# mavroOBD-Power.net
KiCad netlist of a schematic drawn in EAGLE
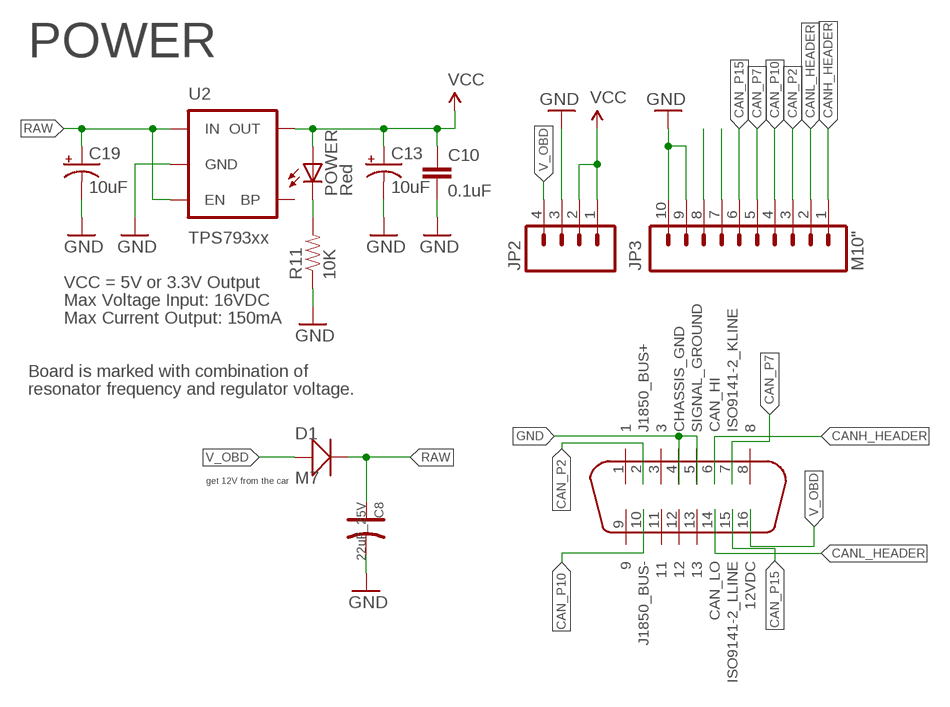
[diagram p0: schematic, sheet 1]

(export (version "E")
  (design (tool "Eeschema 10.0.6"))
  (components
    (comp (ref "C8")
      (value "22uF_25V")
      (footprint "eagle-import:ELECTRO-SMD-B-4.8MM")
      (libsource (lib "eagle-import") (part "CAP-ELECTRO-B"))
    )
    (comp (ref "C10")
      (value "0.1uF")
      (footprint "eagle-import:0603-CAP")
      (libsource (lib "eagle-import") (part "CAP0603-CAP"))
    )
    (comp (ref "C13")
      (value "10uF")
      (footprint "eagle-import:EIA3216")
      (libsource (lib "eagle-import") (part "CAP_POL1206"))
    )
    (comp (ref "C19")
      (value "10uF")
      (footprint "eagle-import:EIA3216")
      (libsource (lib "eagle-import") (part "CAP_POL1206"))
    )
    (comp (ref "D1")
      (value "M7")
      (footprint "eagle-import:D2010")
      (libsource (lib "eagle-import") (part "D-SMA"))
    )
    (comp (ref "JP2")
      (value "M04PTH")
      (footprint "eagle-import:1X04")
      (libsource (lib "eagle-import") (part "M04PTH"))
    )
    (comp (ref "JP3")
      (value "M10\"")
      (footprint "eagle-import:1X10")
      (libsource (lib "eagle-import") (part "M10{dblquote}"))
    )
    (comp (ref "POWER")
      (value "Red")
      (footprint "eagle-import:0603-LED-ALT1")
      (libsource (lib "eagle-import") (part "LED"))
    )
    (comp (ref "R11")
      (value "10K")
      (footprint "eagle-import:0603-RES")
      (libsource (lib "eagle-import") (part "RESISTOR0603-RES"))
    )
    (comp (ref "U$1")
      (value "ODBII-CON")
      (footprint "eagle-import:OBDII-CON")
      (libsource (lib "eagle-import") (part "ODBII-CON"))
    )
    (comp (ref "U2")
      (value "TPS793xx")
      (footprint "eagle-import:SOT23-5")
      (libsource (lib "eagle-import") (part "V_REG_LDOSMD"))
    )
  )
  (nets
    (net (code "1") (name "CANH_HEADER") (class "Default")
      (node (ref "JP3") (pin "1") (pinfunction "1_1") (pintype "passive"))
      (node (ref "U$1") (pin "6") (pinfunction "CAN_HI_6") (pintype "bidirectional"))
    )
    (net (code "2") (name "CANL_HEADER") (class "Default")
      (node (ref "JP3") (pin "2") (pinfunction "2_2") (pintype "passive"))
      (node (ref "U$1") (pin "14") (pinfunction "CAN_LO_14") (pintype "bidirectional"))
    )
    (net (code "3") (name "CAN_P2") (class "Default")
      (node (ref "JP3") (pin "3") (pinfunction "3_3") (pintype "passive"))
      (node (ref "U$1") (pin "2") (pinfunction "J1850_BUS+_2") (pintype "bidirectional"))
    )
    (net (code "4") (name "CAN_P7") (class "Default")
      (node (ref "JP3") (pin "5") (pinfunction "5_5") (pintype "passive"))
      (node (ref "U$1") (pin "7") (pinfunction "ISO9141-2_KLINE_7") (pintype "bidirectional"))
    )
    (net (code "5") (name "CAN_P10") (class "Default")
      (node (ref "JP3") (pin "4") (pinfunction "4_4") (pintype "passive"))
      (node (ref "U$1") (pin "10") (pinfunction "J1850_BUS-_10") (pintype "bidirectional"))
    )
    (net (code "6") (name "CAN_P15") (class "Default")
      (node (ref "JP3") (pin "6") (pinfunction "6_6") (pintype "passive"))
      (node (ref "U$1") (pin "15") (pinfunction "ISO9141-2_LLINE_15") (pintype "bidirectional"))
    )
    (net (code "7") (name "GND") (class "Default")
      (node (ref "C10") (pin "2") (pinfunction "2_2") (pintype "passive"))
      (node (ref "C13") (pin "C") (pinfunction "-_C") (pintype "passive"))
      (node (ref "C19") (pin "C") (pinfunction "-_C") (pintype "passive"))
      (node (ref "C8") (pin "-") (pinfunction "-_-") (pintype "passive"))
      (node (ref "JP2") (pin "3") (pinfunction "3_3") (pintype "passive"))
      (node (ref "JP3") (pin "10") (pinfunction "10_10") (pintype "passive"))
      (node (ref "JP3") (pin "9") (pinfunction "9_9") (pintype "passive"))
      (node (ref "R11") (pin "1") (pinfunction "1_1") (pintype "passive"))
      (node (ref "U$1") (pin "4") (pinfunction "CHASSIS_GND_4") (pintype "bidirectional"))
      (node (ref "U$1") (pin "5") (pinfunction "SIGNAL_GROUND_5") (pintype "bidirectional"))
      (node (ref "U2") (pin "2") (pinfunction "GND_2") (pintype "input"))
    )
    (net (code "8") (name "Net-(POWER-PadC)") (class "Default")
      (node (ref "POWER") (pin "C") (pinfunction "C_C") (pintype "passive"))
      (node (ref "R11") (pin "2") (pinfunction "2_2") (pintype "passive"))
    )
    (net (code "9") (name "RAW") (class "Default")
      (node (ref "C19") (pin "A") (pinfunction "+_A") (pintype "passive"))
      (node (ref "C8") (pin "+") (pinfunction "+_+") (pintype "passive"))
      (node (ref "D1") (pin "-") (pinfunction "-_-") (pintype "passive"))
      (node (ref "U2") (pin "1") (pinfunction "IN_1") (pintype "input"))
      (node (ref "U2") (pin "3") (pinfunction "EN_3") (pintype "input"))
    )
    (net (code "10") (name "VCC") (class "Default")
      (node (ref "C10") (pin "1") (pinfunction "1_1") (pintype "passive"))
      (node (ref "C13") (pin "A") (pinfunction "+_A") (pintype "passive"))
      (node (ref "JP2") (pin "1") (pinfunction "1_1") (pintype "passive"))
      (node (ref "JP2") (pin "2") (pinfunction "2_2") (pintype "passive"))
      (node (ref "POWER") (pin "A") (pinfunction "A_A") (pintype "passive"))
      (node (ref "U2") (pin "5") (pinfunction "OUT_5") (pintype "passive"))
    )
    (net (code "11") (name "V_OBD") (class "Default")
      (node (ref "D1") (pin "+") (pinfunction "+_+") (pintype "passive"))
      (node (ref "JP2") (pin "4") (pinfunction "4_4") (pintype "passive"))
      (node (ref "U$1") (pin "16") (pinfunction "12VDC_16") (pintype "bidirectional"))
    )
    (net (code "12") (name "unconnected-(JP3-Pad7)") (class "Default")
      (node (ref "JP3") (pin "7") (pinfunction "7_7") (pintype "passive"))
    )
    (net (code "13") (name "unconnected-(JP3-Pad8)") (class "Default")
      (node (ref "JP3") (pin "8") (pinfunction "8_8") (pintype "passive"))
    )
    (net (code "14") (name "unconnected-(U$1-Pad1)") (class "Default")
      (node (ref "U$1") (pin "1") (pinfunction "1_1") (pintype "no_connect"))
    )
    (net (code "15") (name "unconnected-(U$1-Pad3)") (class "Default")
      (node (ref "U$1") (pin "3") (pinfunction "3_3") (pintype "no_connect"))
    )
    (net (code "16") (name "unconnected-(U$1-Pad8)") (class "Default")
      (node (ref "U$1") (pin "8") (pinfunction "8_8") (pintype "no_connect"))
    )
    (net (code "17") (name "unconnected-(U$1-Pad9)") (class "Default")
      (node (ref "U$1") (pin "9") (pinfunction "9_9") (pintype "no_connect"))
    )
    (net (code "18") (name "unconnected-(U$1-Pad11)") (class "Default")
      (node (ref "U$1") (pin "11") (pinfunction "11_11") (pintype "no_connect"))
    )
    (net (code "19") (name "unconnected-(U$1-Pad12)") (class "Default")
      (node (ref "U$1") (pin "12") (pinfunction "12_12") (pintype "no_connect"))
    )
    (net (code "20") (name "unconnected-(U$1-Pad13)") (class "Default")
      (node (ref "U$1") (pin "13") (pinfunction "13_13") (pintype "no_connect"))
    )
    (net (code "21") (name "unconnected-(U2-BP-Pad4)") (class "Default")
      (node (ref "U2") (pin "4") (pinfunction "BP_4") (pintype "input"))
    )
  )
)
